# koosh_connector.net
KiCad netlist of a schematic drawn in Altium Designer
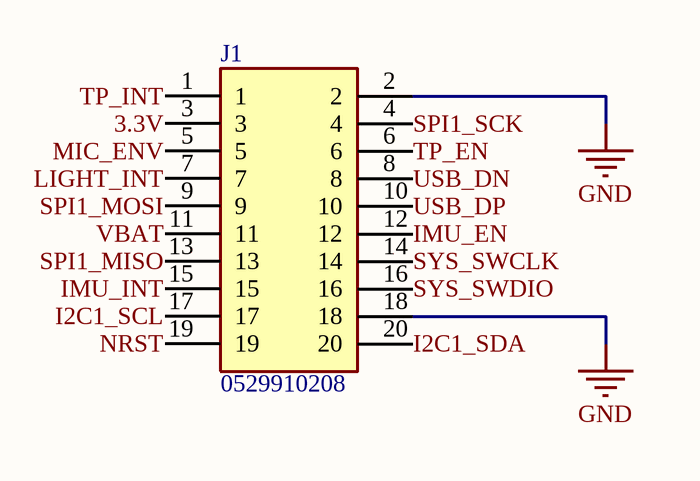
[diagram p0: koosh_connector.SchDoc]

(export (version "E")
  (design (tool "Eeschema 10.0.6"))
  (components
    (comp (ref "J1")
      (value "0529910208")
      (footprint "SamacSys:0529910208")
      (description "Connector")
      (libsource (lib "*") (part "0529910208"))
    )
  )
  (nets
    (net (code "1") (name "/3.3V") (class "Default")
      (node (ref "J1") (pin "3") (pinfunction "3_3") (pintype "passive"))
    )
    (net (code "2") (name "/I2C1_SCL") (class "Default")
      (node (ref "J1") (pin "17") (pinfunction "17_17") (pintype "passive"))
    )
    (net (code "3") (name "/I2C1_SDA") (class "Default")
      (node (ref "J1") (pin "20") (pinfunction "20_20") (pintype "passive"))
    )
    (net (code "4") (name "/IMU_EN") (class "Default")
      (node (ref "J1") (pin "12") (pinfunction "12_12") (pintype "passive"))
    )
    (net (code "5") (name "/IMU_INT") (class "Default")
      (node (ref "J1") (pin "15") (pinfunction "15_15") (pintype "passive"))
    )
    (net (code "6") (name "/LIGHT_INT") (class "Default")
      (node (ref "J1") (pin "7") (pinfunction "7_7") (pintype "passive"))
    )
    (net (code "7") (name "/MIC_ENV") (class "Default")
      (node (ref "J1") (pin "5") (pinfunction "5_5") (pintype "passive"))
    )
    (net (code "8") (name "/NRST") (class "Default")
      (node (ref "J1") (pin "19") (pinfunction "19_19") (pintype "passive"))
    )
    (net (code "9") (name "/SPI1_MISO") (class "Default")
      (node (ref "J1") (pin "13") (pinfunction "13_13") (pintype "passive"))
    )
    (net (code "10") (name "/SPI1_MOSI") (class "Default")
      (node (ref "J1") (pin "9") (pinfunction "9_9") (pintype "passive"))
    )
    (net (code "11") (name "/SPI1_SCK") (class "Default")
      (node (ref "J1") (pin "4") (pinfunction "4_4") (pintype "passive"))
    )
    (net (code "12") (name "/SYS_SWCLK") (class "Default")
      (node (ref "J1") (pin "14") (pinfunction "14_14") (pintype "passive"))
    )
    (net (code "13") (name "/SYS_SWDIO") (class "Default")
      (node (ref "J1") (pin "16") (pinfunction "16_16") (pintype "passive"))
    )
    (net (code "14") (name "/TP_EN") (class "Default")
      (node (ref "J1") (pin "6") (pinfunction "6_6") (pintype "passive"))
    )
    (net (code "15") (name "/TP_INT") (class "Default")
      (node (ref "J1") (pin "1") (pinfunction "1_1") (pintype "passive"))
    )
    (net (code "16") (name "/USB_DN") (class "Default")
      (node (ref "J1") (pin "8") (pinfunction "8_8") (pintype "passive"))
    )
    (net (code "17") (name "/USB_DP") (class "Default")
      (node (ref "J1") (pin "10") (pinfunction "10_10") (pintype "passive"))
    )
    (net (code "18") (name "/VBAT") (class "Default")
      (node (ref "J1") (pin "11") (pinfunction "11_11") (pintype "passive"))
    )
    (net (code "19") (name "GND") (class "Default")
      (node (ref "J1") (pin "18") (pinfunction "18_18") (pintype "passive"))
      (node (ref "J1") (pin "2") (pinfunction "2_2") (pintype "passive"))
    )
  )
)
